# MCU_Main.net
KiCad netlist of a schematic drawn in Altium Designer
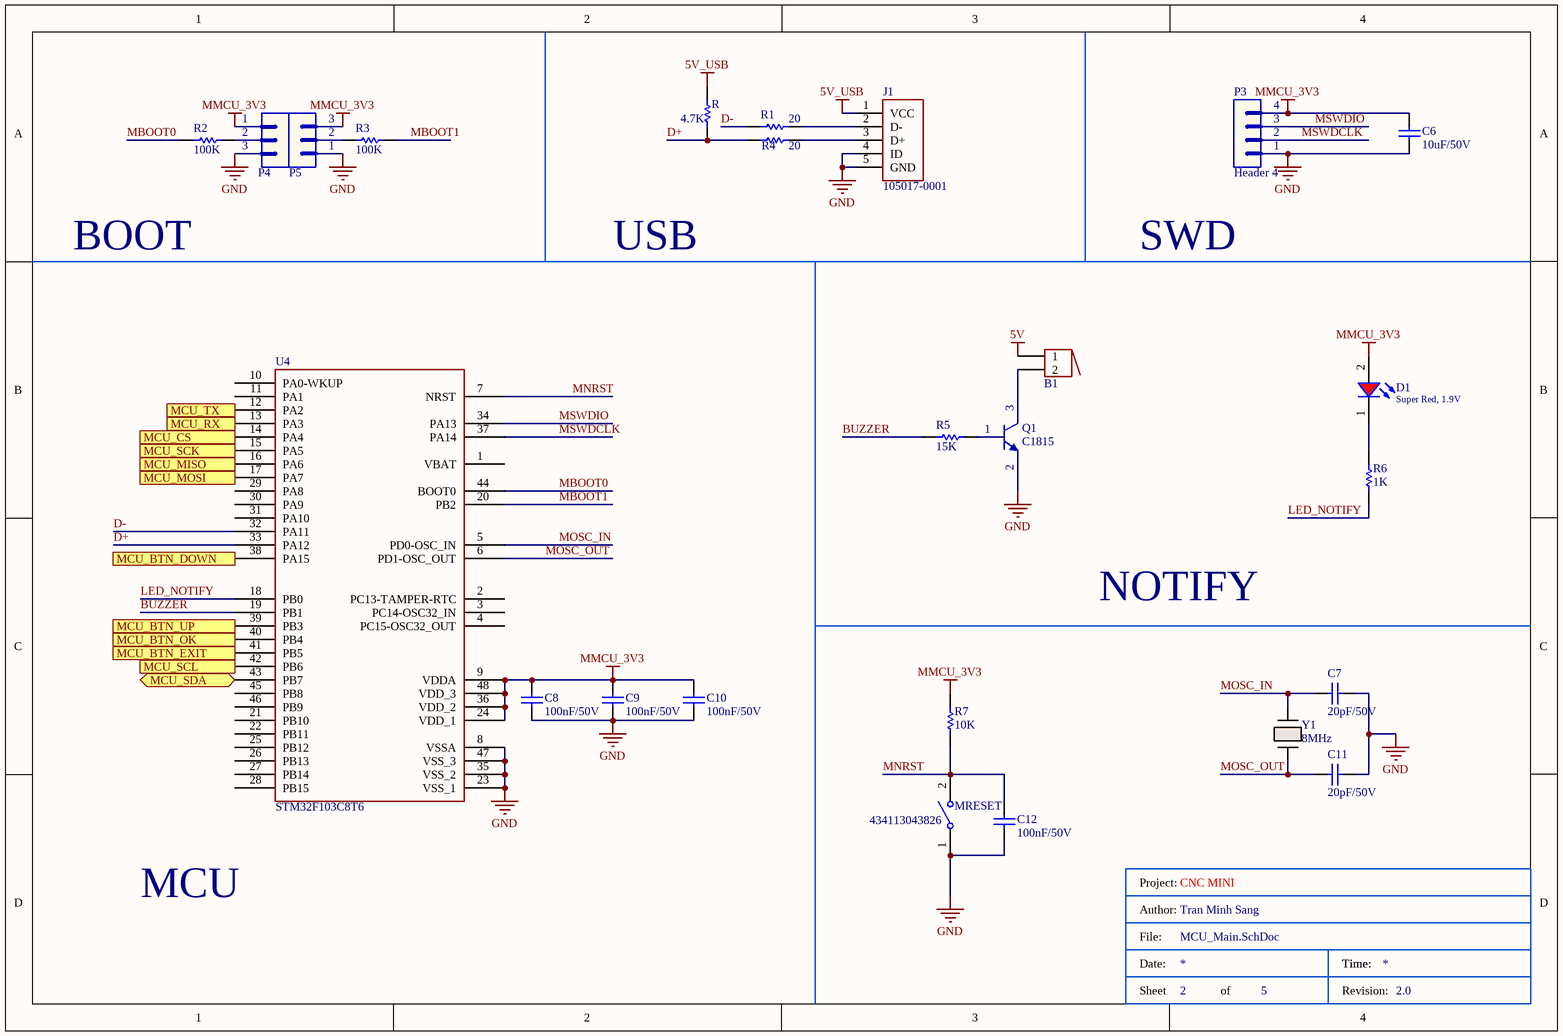
[diagram p0: MCU_Main.SchDoc]

(export (version "E")
  (design (tool "Eeschema 10.0.6"))
  (components
    (comp (ref "B1")
      (value "Buzzer")
      (footprint "BUZZER")
      (fields (field (name "LOCAL SUPPLIER PART NUMBER") "1209 DIP Buzzer 12x9mm"))
      (libsource (lib "MiniCNC_ver2") (part "Buzzer"))
    )
    (comp (ref "C6")
      (value "10uF/50V")
      (footprint "CAP-SM-0805")
      (description "CAP CER 10UF 50V X5R 0805")
      (fields
        (field (name "MANUFACTURER") "Yageo")
        (field (name "MANUFACTURER PART NUMBER") "CC0805KKX5R9BB106")
      )
      (libsource (lib "capacitor-smd") (part "Cap-10uF-50V-0805"))
    )
    (comp (ref "C7")
      (value "20pF/50V")
      (footprint "CAP-SM-0805")
      (description "CAP CER 22PF 100V X7R 0805")
      (fields
        (field (name "MANUFACTURER") "Johanson Dielectrics Inc.")
        (field (name "MANUFACTURER PART NUMBER") "101X15W102MV4E")
      )
      (libsource (lib "capacitor-smd") (part "Cap-22pF-50V-0805"))
    )
    (comp (ref "C8")
      (value "100nF/50V")
      (footprint "CAP-SM-0805")
      (description "CAP CER 0.1UF 50V Y5V 0805")
      (fields
        (field (name "MANUFACTURER") "Samsung Electro-Mechanics")
        (field (name "MANUFACTURER PART NUMBER") "CL21F104ZBCNNNC")
      )
      (libsource (lib "capacitor-smd") (part "Cap-100nF-50V-0805"))
    )
    (comp (ref "C9")
      (value "100nF/50V")
      (footprint "CAP-SM-0805")
      (description "CAP CER 0.1UF 50V Y5V 0805")
      (fields
        (field (name "MANUFACTURER") "Samsung Electro-Mechanics")
        (field (name "MANUFACTURER PART NUMBER") "CL21F104ZBCNNNC")
      )
      (libsource (lib "capacitor-smd") (part "Cap-100nF-50V-0805"))
    )
    (comp (ref "C10")
      (value "100nF/50V")
      (footprint "CAP-SM-0805")
      (description "CAP CER 0.1UF 50V Y5V 0805")
      (fields
        (field (name "MANUFACTURER") "Samsung Electro-Mechanics")
        (field (name "MANUFACTURER PART NUMBER") "CL21F104ZBCNNNC")
      )
      (libsource (lib "capacitor-smd") (part "Cap-100nF-50V-0805"))
    )
    (comp (ref "C11")
      (value "20pF/50V")
      (footprint "CAP-SM-0805")
      (description "CAP CER 22PF 100V X7R 0805")
      (fields
        (field (name "MANUFACTURER") "Johanson Dielectrics Inc.")
        (field (name "MANUFACTURER PART NUMBER") "101X15W102MV4E")
      )
      (libsource (lib "capacitor-smd") (part "Cap-22pF-50V-0805"))
    )
    (comp (ref "C12")
      (value "100nF/50V")
      (footprint "CAP-SM-0805")
      (description "CAP CER 0.1UF 50V Y5V 0805")
      (fields
        (field (name "MANUFACTURER") "Samsung Electro-Mechanics")
        (field (name "MANUFACTURER PART NUMBER") "CL21F104ZBCNNNC")
      )
      (libsource (lib "capacitor-smd") (part "Cap-100nF-50V-0805"))
    )
    (comp (ref "D1")
      (value "Super Red, 1.9V")
      (footprint "WL-SMCW_0805")
      (description "WL-SMCW SMT Mono-color Chip LED Waterclear, size 0805, Super Red, 1.9V, 140deg")
      (fields (field (name "PART NUMBER") "150080SS75000") (field (name "PUBLISHER") "Wurth Elektronik"))
      (libsource (lib "led-smd-0805") (part "150080SS75000"))
    )
    (comp (ref "J1")
      (value "105017-0001")
      (footprint "Micro-USB-Female")
      (description "CONN RCPT USB2.0 MICRO B SMD R/A")
      (fields
        (field (name "LOCAL SUPPLIER PART NUMBER") "x")
        (field (name "COPYRIGHT") "Copyright (C) 2018 Accelerated Designs. All rights reserved")
      )
      (libsource (lib "header-connector") (part "Micro-USB-Female"))
    )
    (comp (ref "MRESET")
      (value "434113043826")
      (footprint "434113043826")
      (description "WS-TASV J-Bend SMT Tact Switch 6x3.5mm, height 4.3mm, 260gf")
      (fields (field (name "LOCAL SUPPLIER PART NUMBER") "x") (field (name "PUBLISHER") "Wurth Elektronik"))
      (libsource (lib "switch") (part "434113043826"))
    )
    (comp (ref "P3")
      (value "Header 4")
      (footprint "JP4")
      (description "Header, 4-Pin")
      (fields (field (name "LOCAL SUPPLIER PART NUMBER") "x") (field (name "PUBLISHER") "Altium Limited"))
      (libsource (lib "header-connector") (part "Header 4"))
    )
    (comp (ref "P4")
      (value "Header 3")
      (footprint "JP3")
      (description "Header, 3-Pin")
      (fields (field (name "LOCAL SUPPLIER PART NUMBER") "x") (field (name "PUBLISHER") "Altium Limited"))
      (libsource (lib "") (part "Header 3_1"))
    )
    (comp (ref "P5")
      (value "Header 3")
      (footprint "JP3")
      (description "Header, 3-Pin")
      (fields (field (name "LOCAL SUPPLIER PART NUMBER") "x") (field (name "PUBLISHER") "Altium Limited"))
      (libsource (lib "header-connector") (part "Header 3"))
    )
    (comp (ref "Q1") (value "C1815") (footprint "SOT23_NEX") (libsource (lib "bjt-smd") (part "C1815")))
    (comp (ref "R")
      (value "4.7K")
      (footprint "resistor-smd:RES-SM-0805")
      (description "RES SMD 4.7K OHM 5% 1/8W 0805")
      (fields
        (field (name "MANUFACTURER") "Yageo")
        (field (name "MANUFACTURER PART NUMBER") "RC0805JR-074K7L")
      )
      (libsource (lib "resistor-smd") (part "Res-4.7K-0805"))
    )
    (comp (ref "R1")
      (value "20")
      (footprint "resistor-smd:RES-SM-0805")
      (description "RES SMD 270 OHM 0.1% 0.15W 0705")
      (fields
        (field (name "MANUFACTURER") "Vishay Dale")
        (field (name "MANUFACTURER PART NUMBER") "M55342E06B270ART5")
      )
      (libsource (lib "resistor-smd") (part "Res-270-0805"))
    )
    (comp (ref "R2")
      (value "100K")
      (footprint "resistor-smd:RES-SM-0805")
      (description "RES 0 OHM JUMPER 0805")
      (fields
        (field (name "MANUFACTURER") "Vishay Dale")
        (field (name "MANUFACTURER PART NUMBER") "WSL080500000ZEA9")
      )
      (libsource (lib "resistor-smd") (part "Res-100K-0805"))
    )
    (comp (ref "R3")
      (value "100K")
      (footprint "resistor-smd:RES-SM-0805")
      (description "RES 0 OHM JUMPER 0805")
      (fields
        (field (name "MANUFACTURER") "Vishay Dale")
        (field (name "MANUFACTURER PART NUMBER") "WSL080500000ZEA9")
      )
      (libsource (lib "resistor-smd") (part "Res-100K-0805"))
    )
    (comp (ref "R4")
      (value "20")
      (footprint "resistor-smd:RES-SM-0805")
      (description "RES SMD 270 OHM 0.1% 0.15W 0705")
      (fields
        (field (name "MANUFACTURER") "Vishay Dale")
        (field (name "MANUFACTURER PART NUMBER") "M55342E06B270ART5")
      )
      (libsource (lib "resistor-smd") (part "Res-270-0805"))
    )
    (comp (ref "R5")
      (value "15K")
      (footprint "resistor-smd:RES-SM-0805")
      (description "RES 15K OHM 1% 1/4W 0805")
      (fields
        (field (name "MANUFACTURER") "TE Connectivity Passive Product")
        (field (name "MANUFACTURER PART NUMBER") "CRGCQ0805F15K")
      )
      (libsource (lib "resistor-smd") (part "Res-15K-0805"))
    )
    (comp (ref "R6")
      (value "1K")
      (footprint "resistor-smd:RES-SM-0805")
      (description "RES 1K OHM 1% 1/4W 0805")
      (fields
        (field (name "MANUFACTURER") "Stackpole Electronics Inc")
        (field (name "MANUFACTURER PART NUMBER") "RNCP0805FTD1K00")
      )
      (libsource (lib "resistor-smd") (part "Res-1K-0805"))
    )
    (comp (ref "R7")
      (value "10K")
      (footprint "resistor-smd:RES-SM-0805")
      (description "RES 10K OHM 1% 1/4W 0805")
      (fields
        (field (name "MANUFACTURER") "Stackpole Electronics Inc")
        (field (name "MANUFACTURER PART NUMBER") "RNCP0805FTD10K0")
      )
      (libsource (lib "resistor-smd") (part "Res-10k-0805"))
    )
    (comp (ref "U4")
      (value "STM32F103C8T6")
      (footprint "LQFP-48")
      (fields (field (name "MANUFACTURER") "ST Electronic"))
      (libsource (lib "MiniCNC_ver2") (part "STM32F103C8T6"))
    )
    (comp (ref "Y1")
      (value "8MHz")
      (footprint "xtal2_CX5032GB_AVX-L")
      (description "No Description Available")
      (fields
        (field (name "MANUFACTURER_PART_NUMBER") "CX5032GB08000H0HEQZ1")
        (field (name "COPYRIGHT") "Copyright (C) 2023 Ultra Librarian. All rights reserved.")
      )
      (libsource (lib "MiniCNC_ver2") (part "XTAL"))
    )
  )
  (nets
    (net (code "1") (name "/BUZZER") (class "Default")
      (node (ref "R5") (pin "1") (pinfunction "1_1") (pintype "passive"))
      (node (ref "U4") (pin "19") (pinfunction "PB1_19") (pintype "passive"))
    )
    (net (code "2") (name "/D+") (class "Default")
      (node (ref "R") (pin "2") (pinfunction "2_2") (pintype "passive"))
      (node (ref "R4") (pin "2") (pinfunction "2_2") (pintype "passive"))
      (node (ref "U4") (pin "33") (pinfunction "PA12_33") (pintype "passive"))
    )
    (net (code "3") (name "/D-") (class "Default")
      (node (ref "R1") (pin "2") (pinfunction "2_2") (pintype "passive"))
      (node (ref "U4") (pin "32") (pinfunction "PA11_32") (pintype "passive"))
    )
    (net (code "4") (name "/LED_NOTIFY") (class "Default")
      (node (ref "R6") (pin "1") (pinfunction "1_1") (pintype "passive"))
      (node (ref "U4") (pin "18") (pinfunction "PB0_18") (pintype "passive"))
    )
    (net (code "5") (name "/MBOOT0") (class "Default")
      (node (ref "R2") (pin "1") (pinfunction "1_1") (pintype "passive"))
      (node (ref "U4") (pin "44") (pinfunction "BOOT0_44") (pintype "passive"))
    )
    (net (code "6") (name "/MBOOT1") (class "Default")
      (node (ref "R3") (pin "2") (pinfunction "2_2") (pintype "passive"))
      (node (ref "U4") (pin "20") (pinfunction "PB2_20") (pintype "passive"))
    )
    (net (code "7") (name "/MCU_BTN_DOWN") (class "Default")
      (node (ref "U4") (pin "38") (pinfunction "PA15_38") (pintype "passive"))
    )
    (net (code "8") (name "/MCU_BTN_EXIT") (class "Default")
      (node (ref "U4") (pin "41") (pinfunction "PB5_41") (pintype "passive"))
    )
    (net (code "9") (name "/MCU_BTN_OK") (class "Default")
      (node (ref "U4") (pin "40") (pinfunction "PB4_40") (pintype "passive"))
    )
    (net (code "10") (name "/MCU_BTN_UP") (class "Default")
      (node (ref "U4") (pin "39") (pinfunction "PB3_39") (pintype "passive"))
    )
    (net (code "11") (name "/MCU_CS") (class "Default")
      (node (ref "U4") (pin "14") (pinfunction "PA4_14") (pintype "passive"))
    )
    (net (code "12") (name "/MCU_MISO") (class "Default")
      (node (ref "U4") (pin "16") (pinfunction "PA6_16") (pintype "passive"))
    )
    (net (code "13") (name "/MCU_MOSI") (class "Default")
      (node (ref "U4") (pin "17") (pinfunction "PA7_17") (pintype "passive"))
    )
    (net (code "14") (name "/MCU_RX") (class "Default")
      (node (ref "U4") (pin "13") (pinfunction "PA3_13") (pintype "passive"))
    )
    (net (code "15") (name "/MCU_SCK") (class "Default")
      (node (ref "U4") (pin "15") (pinfunction "PA5_15") (pintype "passive"))
    )
    (net (code "16") (name "/MCU_SCL") (class "Default")
      (node (ref "U4") (pin "42") (pinfunction "PB6_42") (pintype "passive"))
    )
    (net (code "17") (name "/MCU_SDA") (class "Default")
      (node (ref "U4") (pin "43") (pinfunction "PB7_43") (pintype "passive"))
    )
    (net (code "18") (name "/MCU_TX") (class "Default")
      (node (ref "U4") (pin "12") (pinfunction "PA2_12") (pintype "passive"))
    )
    (net (code "19") (name "/MNRST") (class "Default")
      (node (ref "C12") (pin "2") (pinfunction "2_2") (pintype "passive"))
      (node (ref "MRESET") (pin "2") (pinfunction "2_2") (pintype "passive"))
      (node (ref "R7") (pin "1") (pinfunction "1_1") (pintype "passive"))
      (node (ref "U4") (pin "7") (pinfunction "NRST_7") (pintype "passive"))
    )
    (net (code "20") (name "/MOSC_IN") (class "Default")
      (node (ref "C7") (pin "2") (pinfunction "2_2") (pintype "passive"))
      (node (ref "U4") (pin "5") (pinfunction "PD0-OSC_IN_5") (pintype "passive"))
      (node (ref "Y1") (pin "1") (pinfunction "1_1") (pintype "passive"))
    )
    (net (code "21") (name "/MOSC_OUT") (class "Default")
      (node (ref "C11") (pin "2") (pinfunction "2_2") (pintype "passive"))
      (node (ref "U4") (pin "6") (pinfunction "PD1-OSC_OUT_6") (pintype "passive"))
      (node (ref "Y1") (pin "2") (pinfunction "2_2") (pintype "passive"))
    )
    (net (code "22") (name "/MSWDCLK") (class "Default")
      (node (ref "P3") (pin "2") (pinfunction "2_2") (pintype "passive"))
      (node (ref "U4") (pin "37") (pinfunction "PA14_37") (pintype "passive"))
    )
    (net (code "23") (name "/MSWDIO") (class "Default")
      (node (ref "P3") (pin "3") (pinfunction "3_3") (pintype "passive"))
      (node (ref "U4") (pin "34") (pinfunction "PA13_34") (pintype "passive"))
    )
    (net (code "24") (name "5V") (class "Default")
      (node (ref "B1") (pin "1") (pinfunction "1_1") (pintype "passive"))
    )
    (net (code "25") (name "5V_USB") (class "Default")
      (node (ref "J1") (pin "1") (pinfunction "VCC_1") (pintype "power_in"))
      (node (ref "R") (pin "1") (pinfunction "1_1") (pintype "passive"))
    )
    (net (code "26") (name "GND") (class "Default")
      (node (ref "C10") (pin "2") (pinfunction "2_2") (pintype "passive"))
      (node (ref "C11") (pin "1") (pinfunction "1_1") (pintype "passive"))
      (node (ref "C12") (pin "1") (pinfunction "1_1") (pintype "passive"))
      (node (ref "C6") (pin "1") (pinfunction "1_1") (pintype "passive"))
      (node (ref "C7") (pin "1") (pinfunction "1_1") (pintype "passive"))
      (node (ref "C8") (pin "2") (pinfunction "2_2") (pintype "passive"))
      (node (ref "C9") (pin "2") (pinfunction "2_2") (pintype "passive"))
      (node (ref "J1") (pin "4") (pinfunction "ID_4") (pintype "passive"))
      (node (ref "J1") (pin "5") (pinfunction "GND_5") (pintype "passive"))
      (node (ref "MRESET") (pin "1") (pinfunction "1_1") (pintype "passive"))
      (node (ref "P3") (pin "1") (pinfunction "1_1") (pintype "passive"))
      (node (ref "P4") (pin "3") (pinfunction "3_3") (pintype "passive"))
      (node (ref "P5") (pin "1") (pinfunction "1_1") (pintype "passive"))
      (node (ref "Q1") (pin "2") (pinfunction "E_2") (pintype "passive"))
      (node (ref "U4") (pin "23") (pinfunction "VSS_1_23") (pintype "passive"))
      (node (ref "U4") (pin "35") (pinfunction "VSS_2_35") (pintype "passive"))
      (node (ref "U4") (pin "47") (pinfunction "VSS_3_47") (pintype "passive"))
      (node (ref "U4") (pin "8") (pinfunction "VSSA_8") (pintype "passive"))
    )
    (net (code "27") (name "MMCU_3V3") (class "Default")
      (node (ref "C10") (pin "1") (pinfunction "1_1") (pintype "passive"))
      (node (ref "C6") (pin "2") (pinfunction "2_2") (pintype "passive"))
      (node (ref "C8") (pin "1") (pinfunction "1_1") (pintype "passive"))
      (node (ref "C9") (pin "1") (pinfunction "1_1") (pintype "passive"))
      (node (ref "D1") (pin "2") (pinfunction "A_2") (pintype "passive"))
      (node (ref "P3") (pin "4") (pinfunction "4_4") (pintype "passive"))
      (node (ref "P4") (pin "1") (pinfunction "1_1") (pintype "passive"))
      (node (ref "P5") (pin "3") (pinfunction "3_3") (pintype "passive"))
      (node (ref "R7") (pin "2") (pinfunction "2_2") (pintype "passive"))
      (node (ref "U4") (pin "24") (pinfunction "VDD_1_24") (pintype "passive"))
      (node (ref "U4") (pin "36") (pinfunction "VDD_2_36") (pintype "passive"))
      (node (ref "U4") (pin "48") (pinfunction "VDD_3_48") (pintype "passive"))
      (node (ref "U4") (pin "9") (pinfunction "VDDA_9") (pintype "passive"))
    )
    (net (code "28") (name "Net-(D1-K)") (class "Default")
      (node (ref "D1") (pin "1") (pinfunction "K_1") (pintype "passive"))
      (node (ref "R6") (pin "2") (pinfunction "2_2") (pintype "passive"))
    )
    (net (code "29") (name "Net-(J1-D+)") (class "Default")
      (node (ref "J1") (pin "3") (pinfunction "D+_3") (pintype "passive"))
      (node (ref "R4") (pin "1") (pinfunction "1_1") (pintype "passive"))
    )
    (net (code "30") (name "Net-(J1-D-)") (class "Default")
      (node (ref "J1") (pin "2") (pinfunction "D-_2") (pintype "passive"))
      (node (ref "R1") (pin "1") (pinfunction "1_1") (pintype "passive"))
    )
    (net (code "31") (name "Net-(P4-Pad2)") (class "Default")
      (node (ref "P4") (pin "2") (pinfunction "2_2") (pintype "passive"))
      (node (ref "R2") (pin "2") (pinfunction "2_2") (pintype "passive"))
    )
    (net (code "32") (name "Net-(P5-Pad2)") (class "Default")
      (node (ref "P5") (pin "2") (pinfunction "2_2") (pintype "passive"))
      (node (ref "R3") (pin "1") (pinfunction "1_1") (pintype "passive"))
    )
    (net (code "33") (name "Net-(Q1-B)") (class "Default")
      (node (ref "Q1") (pin "1") (pinfunction "B_1") (pintype "passive"))
      (node (ref "R5") (pin "2") (pinfunction "2_2") (pintype "passive"))
    )
    (net (code "34") (name "Net-(Q1-C)") (class "Default")
      (node (ref "B1") (pin "2") (pinfunction "2_2") (pintype "passive"))
      (node (ref "Q1") (pin "3") (pinfunction "C_3") (pintype "passive"))
    )
    (net (code "35") (name "unconnected-(U4-PA0-WKUP-Pad10)") (class "Default")
      (node (ref "U4") (pin "10") (pinfunction "PA0-WKUP_10") (pintype "passive"))
    )
    (net (code "36") (name "unconnected-(U4-PA1-Pad11)") (class "Default")
      (node (ref "U4") (pin "11") (pinfunction "PA1_11") (pintype "passive"))
    )
    (net (code "37") (name "unconnected-(U4-PA8-Pad29)") (class "Default")
      (node (ref "U4") (pin "29") (pinfunction "PA8_29") (pintype "passive"))
    )
    (net (code "38") (name "unconnected-(U4-PA9-Pad30)") (class "Default")
      (node (ref "U4") (pin "30") (pinfunction "PA9_30") (pintype "passive"))
    )
    (net (code "39") (name "unconnected-(U4-PA10-Pad31)") (class "Default")
      (node (ref "U4") (pin "31") (pinfunction "PA10_31") (pintype "passive"))
    )
    (net (code "40") (name "unconnected-(U4-PB8-Pad45)") (class "Default")
      (node (ref "U4") (pin "45") (pinfunction "PB8_45") (pintype "passive"))
    )
    (net (code "41") (name "unconnected-(U4-PB9-Pad46)") (class "Default")
      (node (ref "U4") (pin "46") (pinfunction "PB9_46") (pintype "passive"))
    )
    (net (code "42") (name "unconnected-(U4-PB10-Pad21)") (class "Default")
      (node (ref "U4") (pin "21") (pinfunction "PB10_21") (pintype "passive"))
    )
    (net (code "43") (name "unconnected-(U4-PB11-Pad22)") (class "Default")
      (node (ref "U4") (pin "22") (pinfunction "PB11_22") (pintype "passive"))
    )
    (net (code "44") (name "unconnected-(U4-PB12-Pad25)") (class "Default")
      (node (ref "U4") (pin "25") (pinfunction "PB12_25") (pintype "passive"))
    )
    (net (code "45") (name "unconnected-(U4-PB13-Pad26)") (class "Default")
      (node (ref "U4") (pin "26") (pinfunction "PB13_26") (pintype "passive"))
    )
    (net (code "46") (name "unconnected-(U4-PB14-Pad27)") (class "Default")
      (node (ref "U4") (pin "27") (pinfunction "PB14_27") (pintype "passive"))
    )
    (net (code "47") (name "unconnected-(U4-PB15-Pad28)") (class "Default")
      (node (ref "U4") (pin "28") (pinfunction "PB15_28") (pintype "passive"))
    )
    (net (code "48") (name "unconnected-(U4-PC13-TAMPER-RTC-Pad2)") (class "Default")
      (node (ref "U4") (pin "2") (pinfunction "PC13-TAMPER-RTC_2") (pintype "passive"))
    )
    (net (code "49") (name "unconnected-(U4-PC14-OSC32_IN-Pad3)") (class "Default")
      (node (ref "U4") (pin "3") (pinfunction "PC14-OSC32_IN_3") (pintype "passive"))
    )
    (net (code "50") (name "unconnected-(U4-PC15-OSC32_OUT-Pad4)") (class "Default")
      (node (ref "U4") (pin "4") (pinfunction "PC15-OSC32_OUT_4") (pintype "passive"))
    )
    (net (code "51") (name "unconnected-(U4-VBAT-Pad1)") (class "Default")
      (node (ref "U4") (pin "1") (pinfunction "VBAT_1") (pintype "passive"))
    )
  )
)
